# Controller_Board_Interface.net
KiCad netlist of a schematic drawn in Altium Designer
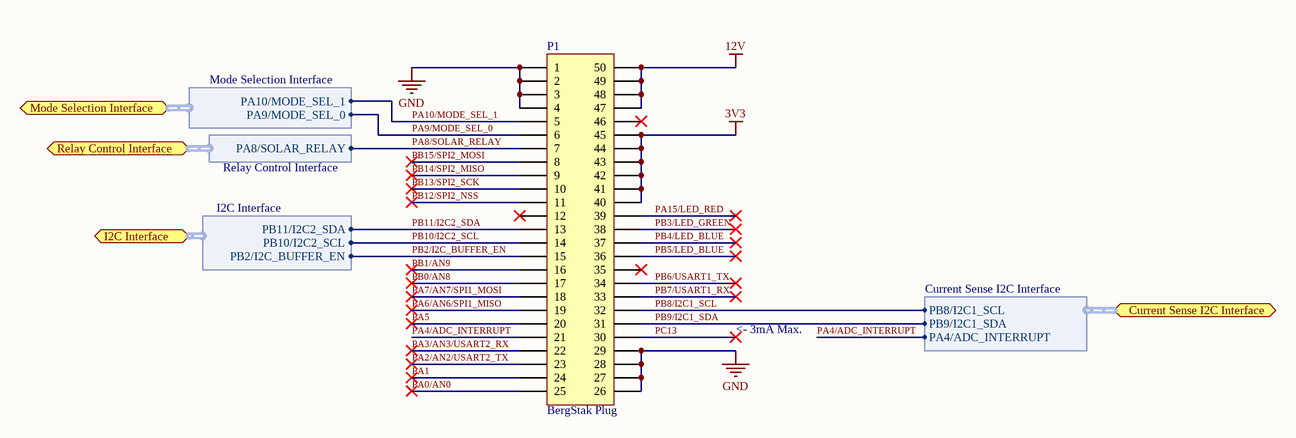
[diagram p0: Controller_Board_Interface.SchDoc]

(export (version "E")
  (design (tool "Eeschema 10.0.6"))
  (components
    (comp (ref "P1")
      (value "CONN 50POS Bergstak Plug 0.02\"")
      (footprint "CONN, Bergstak 50 Pos Plug")
      (description "50 Position Connector Plug, Outer Shroud Contacts Surface Mount Gold")
      (fields (field (name "SERIES") "BergStak Plug"))
      (libsource (lib "Schematic Diagrams") (part "CONN 50POS Bergstak Plug 0.02{dblquote}"))
    )
  )
  (nets
    (net (code "9") (name "/PA0{slash}AN0") (class "Default")
      (node (ref "P1") (pin "25") (pinfunction "25_25") (pintype "passive+no_connect"))
    )
    (net (code "10") (name "/PA1") (class "Default")
      (node (ref "P1") (pin "24") (pinfunction "24_24") (pintype "passive+no_connect"))
    )
    (net (code "11") (name "/PA2{slash}AN2{slash}USART2_TX") (class "Default")
      (node (ref "P1") (pin "23") (pinfunction "23_23") (pintype "passive+no_connect"))
    )
    (net (code "12") (name "/PA3{slash}AN3{slash}USART2_RX") (class "Default")
      (node (ref "P1") (pin "22") (pinfunction "22_22") (pintype "passive+no_connect"))
    )
    (net (code "13") (name "/PA4{slash}ADC_INTERRUPT") (class "Default")
      (node (ref "P1") (pin "21") (pinfunction "21_21") (pintype "passive"))
    )
    (net (code "14") (name "/PA5") (class "Default")
      (node (ref "P1") (pin "20") (pinfunction "20_20") (pintype "passive+no_connect"))
    )
    (net (code "15") (name "/PA6{slash}AN6{slash}SPI1_MISO") (class "Default")
      (node (ref "P1") (pin "19") (pinfunction "19_19") (pintype "passive+no_connect"))
    )
    (net (code "16") (name "/PA7{slash}AN7{slash}SPI1_MOSI") (class "Default")
      (node (ref "P1") (pin "18") (pinfunction "18_18") (pintype "passive+no_connect"))
    )
    (net (code "17") (name "/PA8{slash}SOLAR_RELAY") (class "Default")
      (node (ref "P1") (pin "7") (pinfunction "7_7") (pintype "passive"))
    )
    (net (code "18") (name "/PA9{slash}MODE_SEL_0") (class "Default")
      (node (ref "P1") (pin "6") (pinfunction "6_6") (pintype "passive"))
    )
    (net (code "19") (name "/PA10{slash}MODE_SEL_1") (class "Default")
      (node (ref "P1") (pin "5") (pinfunction "5_5") (pintype "passive"))
    )
    (net (code "20") (name "/PA15{slash}LED_RED") (class "Default")
      (node (ref "P1") (pin "39") (pinfunction "39_39") (pintype "passive+no_connect"))
    )
    (net (code "21") (name "/PB0{slash}AN8") (class "Default")
      (node (ref "P1") (pin "17") (pinfunction "17_17") (pintype "passive+no_connect"))
    )
    (net (code "22") (name "/PB1{slash}AN9") (class "Default")
      (node (ref "P1") (pin "16") (pinfunction "16_16") (pintype "passive+no_connect"))
    )
    (net (code "23") (name "/PB2{slash}I2C_BUFFER_EN") (class "Default")
      (node (ref "P1") (pin "15") (pinfunction "15_15") (pintype "passive"))
    )
    (net (code "24") (name "/PB3{slash}LED_GREEN") (class "Default")
      (node (ref "P1") (pin "38") (pinfunction "38_38") (pintype "passive+no_connect"))
    )
    (net (code "25") (name "/PB4{slash}LED_BLUE") (class "Default")
      (node (ref "P1") (pin "37") (pinfunction "37_37") (pintype "passive+no_connect"))
    )
    (net (code "26") (name "/PB5{slash}LED_BLUE") (class "Default")
      (node (ref "P1") (pin "36") (pinfunction "36_36") (pintype "passive+no_connect"))
    )
    (net (code "27") (name "/PB6{slash}USART1_TX") (class "Default")
      (node (ref "P1") (pin "34") (pinfunction "34_34") (pintype "passive+no_connect"))
    )
    (net (code "28") (name "/PB7{slash}USART1_RX") (class "Default")
      (node (ref "P1") (pin "33") (pinfunction "33_33") (pintype "passive+no_connect"))
    )
    (net (code "29") (name "/PB8{slash}I2C1_SCL") (class "Default")
      (node (ref "P1") (pin "32") (pinfunction "32_32") (pintype "passive"))
    )
    (net (code "30") (name "/PB9{slash}I2C1_SDA") (class "Default")
      (node (ref "P1") (pin "31") (pinfunction "31_31") (pintype "passive"))
    )
    (net (code "31") (name "/PB10{slash}I2C2_SCL") (class "Default")
      (node (ref "P1") (pin "14") (pinfunction "14_14") (pintype "passive"))
    )
    (net (code "32") (name "/PB11{slash}I2C2_SDA") (class "Default")
      (node (ref "P1") (pin "13") (pinfunction "13_13") (pintype "passive"))
    )
    (net (code "33") (name "/PB12{slash}SPI2_NSS") (class "Default")
      (node (ref "P1") (pin "11") (pinfunction "11_11") (pintype "passive+no_connect"))
    )
    (net (code "34") (name "/PB13{slash}SPI2_SCK") (class "Default")
      (node (ref "P1") (pin "10") (pinfunction "10_10") (pintype "passive+no_connect"))
    )
    (net (code "35") (name "/PB14{slash}SPI2_MISO") (class "Default")
      (node (ref "P1") (pin "9") (pinfunction "9_9") (pintype "passive+no_connect"))
    )
    (net (code "36") (name "/PB15{slash}SPI2_MOSI") (class "Default")
      (node (ref "P1") (pin "8") (pinfunction "8_8") (pintype "passive+no_connect"))
    )
    (net (code "37") (name "/PC13") (class "Default")
      (node (ref "P1") (pin "30") (pinfunction "30_30") (pintype "passive+no_connect"))
    )
    (net (code "42") (name "3V3") (class "Default")
      (node (ref "P1") (pin "40") (pinfunction "40_40") (pintype "passive"))
      (node (ref "P1") (pin "41") (pinfunction "41_41") (pintype "passive"))
      (node (ref "P1") (pin "42") (pinfunction "42_42") (pintype "passive"))
      (node (ref "P1") (pin "43") (pinfunction "43_43") (pintype "passive"))
      (node (ref "P1") (pin "44") (pinfunction "44_44") (pintype "passive"))
      (node (ref "P1") (pin "45") (pinfunction "45_45") (pintype "passive"))
    )
    (net (code "43") (name "12V") (class "Default")
      (node (ref "P1") (pin "47") (pinfunction "47_47") (pintype "passive"))
      (node (ref "P1") (pin "48") (pinfunction "48_48") (pintype "passive"))
      (node (ref "P1") (pin "49") (pinfunction "49_49") (pintype "passive"))
      (node (ref "P1") (pin "50") (pinfunction "50_50") (pintype "passive"))
    )
    (net (code "44") (name "GND") (class "Default")
      (node (ref "P1") (pin "1") (pinfunction "1_1") (pintype "passive"))
      (node (ref "P1") (pin "2") (pinfunction "2_2") (pintype "passive"))
      (node (ref "P1") (pin "26") (pinfunction "26_26") (pintype "passive"))
      (node (ref "P1") (pin "27") (pinfunction "27_27") (pintype "passive"))
      (node (ref "P1") (pin "28") (pinfunction "28_28") (pintype "passive"))
      (node (ref "P1") (pin "29") (pinfunction "29_29") (pintype "passive"))
      (node (ref "P1") (pin "3") (pinfunction "3_3") (pintype "passive"))
      (node (ref "P1") (pin "4") (pinfunction "4_4") (pintype "passive"))
    )
    (net (code "45") (name "unconnected-(P1-Pad12)") (class "Default")
      (node (ref "P1") (pin "12") (pinfunction "12_12") (pintype "passive+no_connect"))
    )
    (net (code "46") (name "unconnected-(P1-Pad35)") (class "Default")
      (node (ref "P1") (pin "35") (pinfunction "35_35") (pintype "passive+no_connect"))
    )
    (net (code "47") (name "unconnected-(P1-Pad46)") (class "Default")
      (node (ref "P1") (pin "46") (pinfunction "46_46") (pintype "passive+no_connect"))
    )
  )
)
